# SparkFun_ESP8266_Thing_v10.net
KiCad netlist of a schematic drawn in EAGLE
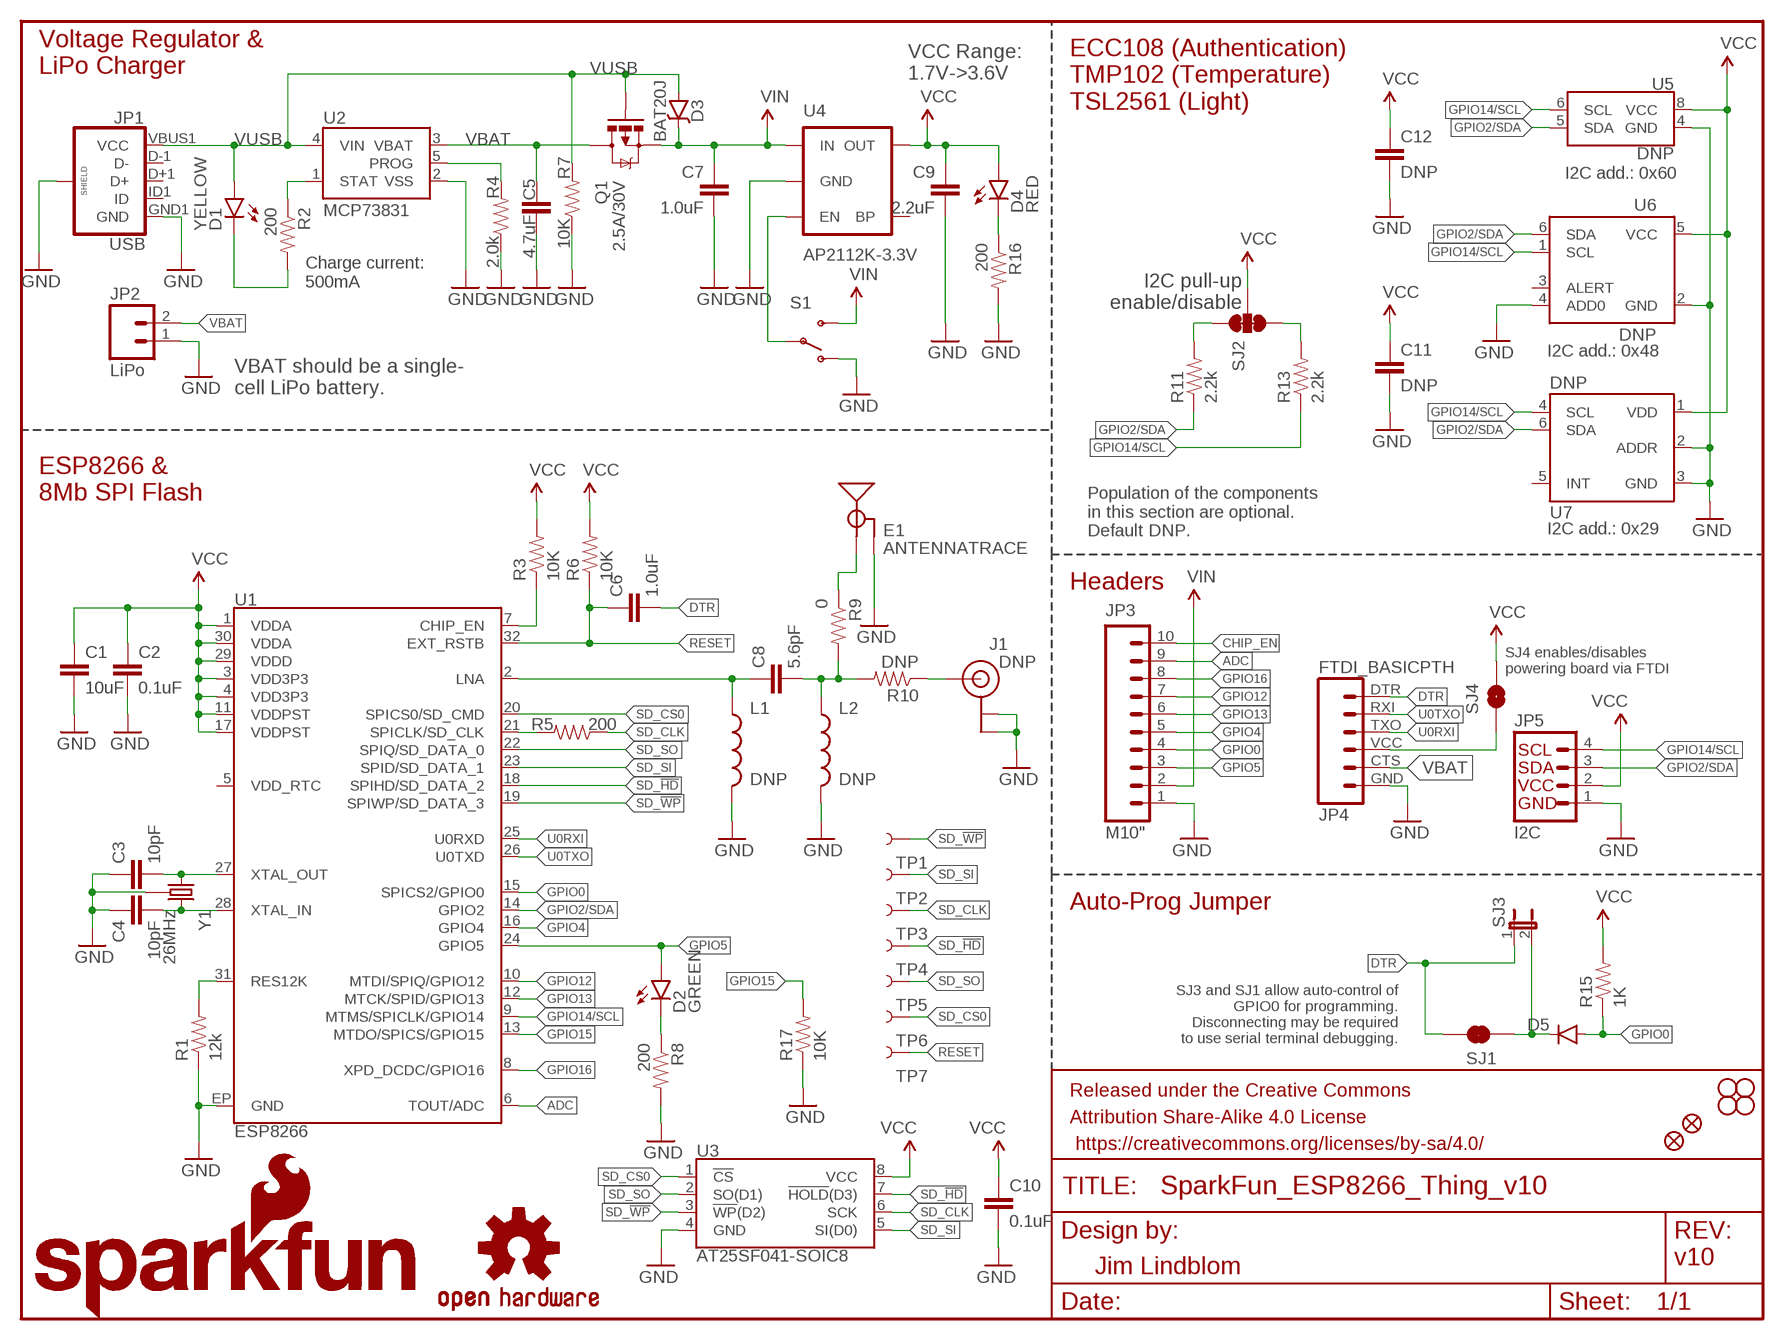
[diagram p0: schematic, sheet 1]

(export (version "E")
  (design (tool "Eeschema 10.0.6"))
  (components
    (comp (ref "C1")
      (value "10uF")
      (footprint "eagle-import:0603-CAP")
      (libsource (lib "eagle-import") (part "10UF-6.3V-20%(0603)"))
    )
    (comp (ref "C2")
      (value "0.1uF")
      (footprint "eagle-import:0603-CAP")
      (libsource (lib "eagle-import") (part "0.1UF-25V(+80/-20%)(0603)"))
    )
    (comp (ref "C3")
      (value "10pF")
      (footprint "eagle-import:0603-CAP")
      (libsource (lib "eagle-import") (part "10PF-50V-5%(0603)"))
    )
    (comp (ref "C4")
      (value "10pF")
      (footprint "eagle-import:0603-CAP")
      (libsource (lib "eagle-import") (part "10PF-50V-5%(0603)"))
    )
    (comp (ref "C5")
      (value "4.7uF")
      (footprint "eagle-import:0603-CAP")
      (libsource (lib "eagle-import") (part "4.7UF-6.3V-10%(0603)0603"))
    )
    (comp (ref "C6")
      (value "1.0uF")
      (footprint "eagle-import:0603-CAP")
      (libsource (lib "eagle-import") (part "1.0UF-16V-10%(0603)"))
    )
    (comp (ref "C7")
      (value "1.0uF")
      (footprint "eagle-import:0805")
      (libsource (lib "eagle-import") (part "1.0UF-25V-+80/-20(0805)"))
    )
    (comp (ref "C8")
      (value "5.6pF")
      (footprint "eagle-import:0603-CAP")
      (libsource (lib "eagle-import") (part "CAP0603-CAP"))
    )
    (comp (ref "C9")
      (value "2.2uF")
      (footprint "eagle-import:0603-CAP")
      (libsource (lib "eagle-import") (part "2.2UF-10V-20%(0603)"))
    )
    (comp (ref "C10")
      (value "0.1uF")
      (footprint "eagle-import:0603-CAP")
      (libsource (lib "eagle-import") (part "0.1UF-25V(+80/-20%)(0603)"))
    )
    (comp (ref "C11")
      (value "DNP")
      (footprint "eagle-import:0603-CAP")
      (libsource (lib "eagle-import") (part "0.1UF-25V(+80/-20%)(0603)"))
    )
    (comp (ref "C12")
      (value "DNP")
      (footprint "eagle-import:0603-CAP")
      (libsource (lib "eagle-import") (part "0.1UF-25V(+80/-20%)(0603)"))
    )
    (comp (ref "D1")
      (value "YELLOW")
      (footprint "eagle-import:LED-0603")
      (libsource (lib "eagle-import") (part "LED-YELLOW0603"))
    )
    (comp (ref "D2")
      (value "GREEN")
      (footprint "eagle-import:LED-0603")
      (libsource (lib "eagle-import") (part "LED-GREEN0603"))
    )
    (comp (ref "D3")
      (value "BAT20J")
      (footprint "eagle-import:SOD-323")
      (libsource (lib "eagle-import") (part "DIODE-SCHOTTKY-BAT20J"))
    )
    (comp (ref "D4")
      (value "RED")
      (footprint "eagle-import:LED-0603")
      (libsource (lib "eagle-import") (part "LED-RED0603"))
    )
    (comp (ref "D5")
      (value "DIODEBAS16")
      (footprint "eagle-import:SOD-323")
      (libsource (lib "eagle-import") (part "DIODEBAS16"))
    )
    (comp (ref "E1")
      (value "ANTENNATRACE")
      (footprint "eagle-import:TRACE_ANTENNA_2.4GHZ_25.7MM")
      (libsource (lib "eagle-import") (part "ANTENNATRACE"))
    )
    (comp (ref "FID1")
      (value "FIDUCIAL1X2")
      (footprint "eagle-import:FIDUCIAL-1X2")
      (libsource (lib "eagle-import") (part "FIDUCIAL1X2"))
    )
    (comp (ref "FID2")
      (value "FIDUCIAL1X2")
      (footprint "eagle-import:FIDUCIAL-1X2")
      (libsource (lib "eagle-import") (part "FIDUCIAL1X2"))
    )
    (comp (ref "FRAME1")
      (value "FRAME-LETTER")
      (footprint "eagle-import:CREATIVE_COMMONS")
      (libsource (lib "eagle-import") (part "FRAME-LETTER"))
    )
    (comp (ref "J1")
      (value "DNP")
      (footprint "eagle-import:U.FL")
      (libsource (lib "eagle-import") (part "U.FL"))
    )
    (comp (ref "JP1")
      (value "USB")
      (footprint "eagle-import:USB-B-MICRO-SMD_V03")
      (libsource (lib "eagle-import") (part "USB_MICROB_PLUGCONN-11752"))
    )
    (comp (ref "JP2")
      (value "LiPo")
      (footprint "eagle-import:JST-2-PTH")
      (libsource (lib "eagle-import") (part "M02JST-PTH-2"))
    )
    (comp (ref "JP3")
      (value "M10\"")
      (footprint "eagle-import:1X10")
      (libsource (lib "eagle-import") (part "M10{dblquote}"))
    )
    (comp (ref "JP4")
      (value "FTDI_BASICPTH")
      (footprint "eagle-import:FTDI_BASIC")
      (libsource (lib "eagle-import") (part "FTDI_BASICPTH"))
    )
    (comp (ref "JP5")
      (value "I2C")
      (footprint "eagle-import:1X04")
      (libsource (lib "eagle-import") (part "I2C_STANDARD"))
    )
    (comp (ref "L1")
      (value "DNP")
      (footprint "eagle-import:0603")
      (libsource (lib "eagle-import") (part "INDUCTOR0603"))
    )
    (comp (ref "L2")
      (value "DNP")
      (footprint "eagle-import:0603")
      (libsource (lib "eagle-import") (part "INDUCTOR0603"))
    )
    (comp (ref "LOGO1")
      (value "SFE_LOGO_NAME.2_INCH")
      (footprint "eagle-import:SFE_LOGO_NAME_.2")
      (libsource (lib "eagle-import") (part "SFE_LOGO_NAME.2_INCH"))
    )
    (comp (ref "LOGO3")
      (value "SFE_LOGO_FLAME.1_INCH")
      (footprint "eagle-import:SFE_LOGO_FLAME_.1")
      (libsource (lib "eagle-import") (part "SFE_LOGO_FLAME.1_INCH"))
    )
    (comp (ref "LOGO4")
      (value "OSHW-LOGOS")
      (footprint "eagle-import:OSHW-LOGO-S")
      (libsource (lib "eagle-import") (part "OSHW-LOGOS"))
    )
    (comp (ref "Q1")
      (value "2.5A/30V")
      (footprint "eagle-import:SOT23-3")
      (libsource (lib "eagle-import") (part "MOSFET-PCHANNELDMG2307L"))
    )
    (comp (ref "R1")
      (value "12k")
      (footprint "eagle-import:0603-RES")
      (libsource (lib "eagle-import") (part "12KOHM-1/10W-1%(0603)"))
    )
    (comp (ref "R2")
      (value "200")
      (footprint "eagle-import:0603-RES")
      (libsource (lib "eagle-import") (part "200OHM1/10W1%(0603)"))
    )
    (comp (ref "R3")
      (value "10K")
      (footprint "eagle-import:0603-RES")
      (libsource (lib "eagle-import") (part "10KOHM1/10W1%(0603)0603"))
    )
    (comp (ref "R4")
      (value "2.0k")
      (footprint "eagle-import:0603-RES")
      (libsource (lib "eagle-import") (part "2.0KOHM1/10W5%(0603)"))
    )
    (comp (ref "R5")
      (value "200")
      (footprint "eagle-import:0603-RES")
      (libsource (lib "eagle-import") (part "200OHM1/10W1%(0603)"))
    )
    (comp (ref "R6")
      (value "10K")
      (footprint "eagle-import:0603-RES")
      (libsource (lib "eagle-import") (part "10KOHM1/10W1%(0603)0603"))
    )
    (comp (ref "R7")
      (value "10K")
      (footprint "eagle-import:0603-RES")
      (libsource (lib "eagle-import") (part "10KOHM1/10W1%(0603)0603"))
    )
    (comp (ref "R8")
      (value "200")
      (footprint "eagle-import:0603-RES")
      (libsource (lib "eagle-import") (part "200OHM1/10W1%(0603)"))
    )
    (comp (ref "R9")
      (value "0")
      (footprint "eagle-import:0603")
      (libsource (lib "eagle-import") (part "0OHM1/10W5%(0603)"))
    )
    (comp (ref "R10")
      (value "DNP")
      (footprint "eagle-import:0603-RES")
      (libsource (lib "eagle-import") (part "RESISTOR0603-RES"))
    )
    (comp (ref "R11")
      (value "2.2k")
      (footprint "eagle-import:0603-RES")
      (libsource (lib "eagle-import") (part "2.2KOHM1/10W1%(0603)"))
    )
    (comp (ref "R13")
      (value "2.2k")
      (footprint "eagle-import:0603-RES")
      (libsource (lib "eagle-import") (part "2.2KOHM1/10W1%(0603)"))
    )
    (comp (ref "R15")
      (value "1K")
      (footprint "eagle-import:0603-RES")
      (libsource (lib "eagle-import") (part "1KOHM1/10W1%(0603)"))
    )
    (comp (ref "R16")
      (value "200")
      (footprint "eagle-import:0603-RES")
      (libsource (lib "eagle-import") (part "200OHM1/10W1%(0603)"))
    )
    (comp (ref "R17")
      (value "10K")
      (footprint "eagle-import:0603-RES")
      (libsource (lib "eagle-import") (part "10KOHM1/10W1%(0603)0603"))
    )
    (comp (ref "S1")
      (value "SWITCH-SPDT-SMD-A")
      (footprint "eagle-import:SWITCH-SPST-SMD-A")
      (libsource (lib "eagle-import") (part "SWITCH-SPDT-SMD-A"))
    )
    (comp (ref "SJ1")
      (value "JUMPER-PAD-2-NC_BY_TRACE")
      (footprint "eagle-import:PAD-JUMPER-2-NC_BY_TRACE_YES_SILK")
      (libsource (lib "eagle-import") (part "JUMPER-PAD-2-NC_BY_TRACE"))
    )
    (comp (ref "SJ2")
      (value "JUMPER-PAD-3-NC_BY_TRACE")
      (footprint "eagle-import:PAD-JUMPER-3-3OF3_NC_BY_TRACE_YES_SILK_FULL_BOX")
      (libsource (lib "eagle-import") (part "JUMPER-PAD-3-NC_BY_TRACE"))
    )
    (comp (ref "SJ3")
      (value "JUMPER-PTH-2-NC")
      (footprint "eagle-import:PTH-JUMPER-NC_BOTTOM_NO_SILK")
      (libsource (lib "eagle-import") (part "JUMPER-PTH-2-NC"))
    )
    (comp (ref "SJ4")
      (value "JUMPER-PAD-2-NOYES_SILK")
      (footprint "eagle-import:PAD-JUMPER-2-NO_YES_SILK")
      (libsource (lib "eagle-import") (part "JUMPER-PAD-2-NOYES_SILK"))
    )
    (comp (ref "STANDOFF1")
      (value "STAND-OFF")
      (footprint "eagle-import:STAND-OFF")
      (libsource (lib "eagle-import") (part "STAND-OFF"))
    )
    (comp (ref "STANDOFF2")
      (value "STAND-OFF")
      (footprint "eagle-import:STAND-OFF")
      (libsource (lib "eagle-import") (part "STAND-OFF"))
    )
    (comp (ref "STANDOFF3")
      (value "STAND-OFF")
      (footprint "eagle-import:STAND-OFF")
      (libsource (lib "eagle-import") (part "STAND-OFF"))
    )
    (comp (ref "STANDOFF4")
      (value "STAND-OFF")
      (footprint "eagle-import:STAND-OFF")
      (libsource (lib "eagle-import") (part "STAND-OFF"))
    )
    (comp (ref "TP1")
      (value "TEST-POINT3X5")
      (footprint "eagle-import:PAD.03X.05")
      (libsource (lib "eagle-import") (part "TEST-POINT3X5"))
    )
    (comp (ref "TP2")
      (value "TEST-POINT3X5")
      (footprint "eagle-import:PAD.03X.05")
      (libsource (lib "eagle-import") (part "TEST-POINT3X5"))
    )
    (comp (ref "TP3")
      (value "TEST-POINT3X5")
      (footprint "eagle-import:PAD.03X.05")
      (libsource (lib "eagle-import") (part "TEST-POINT3X5"))
    )
    (comp (ref "TP4")
      (value "TEST-POINT3X5")
      (footprint "eagle-import:PAD.03X.05")
      (libsource (lib "eagle-import") (part "TEST-POINT3X5"))
    )
    (comp (ref "TP5")
      (value "TEST-POINT3X5")
      (footprint "eagle-import:PAD.03X.05")
      (libsource (lib "eagle-import") (part "TEST-POINT3X5"))
    )
    (comp (ref "TP6")
      (value "TEST-POINT3X5")
      (footprint "eagle-import:PAD.03X.05")
      (libsource (lib "eagle-import") (part "TEST-POINT3X5"))
    )
    (comp (ref "TP7")
      (value "TEST-POINT3X5")
      (footprint "eagle-import:PAD.03X.05")
      (libsource (lib "eagle-import") (part "TEST-POINT3X5"))
    )
    (comp (ref "U1")
      (value "ESP8266")
      (footprint "eagle-import:QFN32")
      (libsource (lib "eagle-import") (part "ESP8266"))
    )
    (comp (ref "U2")
      (value "MCP73831")
      (footprint "eagle-import:SOT23-5")
      (libsource (lib "eagle-import") (part "MCP73831"))
    )
    (comp (ref "U3")
      (value "AT25SF041-SOIC8")
      (footprint "eagle-import:SO08")
      (libsource (lib "eagle-import") (part "AT25SF041-SOIC8"))
    )
    (comp (ref "U4")
      (value "AP2112K-3.3V")
      (footprint "eagle-import:SOT23-5")
      (libsource (lib "eagle-import") (part "V_REG_LDOSMD"))
    )
    (comp (ref "U5")
      (value "DNP")
      (footprint "eagle-import:UDFN8")
      (libsource (lib "eagle-import") (part "ATECC108-MAHDA"))
    )
    (comp (ref "U6")
      (value "DNP")
      (footprint "eagle-import:SOT563-2")
      (libsource (lib "eagle-import") (part "TMP1021{colon}1"))
    )
    (comp (ref "U7")
      (value "DNP")
      (footprint "eagle-import:FN-6")
      (libsource (lib "eagle-import") (part "TSL2561FN"))
    )
    (comp (ref "Y1")
      (value "26MHz")
      (footprint "eagle-import:CRYSTAL-SMD-3.2X2.5")
      (libsource (lib "eagle-import") (part "CRYSTAL-GROUNDED3.2X2.5"))
    )
  )
  (nets
    (net (code "1") (name "/SD_~{HD}") (class "Default")
      (node (ref "TP4") (pin "P$1") (pinfunction "1_P$1") (pintype "bidirectional"))
      (node (ref "U1") (pin "18") (pinfunction "SPIHD/SD_DATA_2_18") (pintype "bidirectional"))
      (node (ref "U3") (pin "7") (pinfunction "~{HOLD}(D3)_7") (pintype "bidirectional"))
    )
    (net (code "2") (name "/SD_~{WP}") (class "Default")
      (node (ref "TP1") (pin "P$1") (pinfunction "1_P$1") (pintype "bidirectional"))
      (node (ref "U1") (pin "19") (pinfunction "SPIWP/SD_DATA_3_19") (pintype "bidirectional"))
      (node (ref "U3") (pin "3") (pinfunction "~{WP}(D2)_3") (pintype "bidirectional"))
    )
    (net (code "3") (name "/VUSB") (class "Default")
      (node (ref "D1") (pin "A") (pinfunction "A_A") (pintype "passive"))
      (node (ref "D3") (pin "A") (pinfunction "A_A") (pintype "passive"))
      (node (ref "JP1") (pin "VBUS1") (pinfunction "VCC_VBUS1") (pintype "bidirectional"))
      (node (ref "Q1") (pin "1") (pinfunction "G_1") (pintype "passive"))
      (node (ref "R7") (pin "2") (pinfunction "2_2") (pintype "passive"))
      (node (ref "U2") (pin "4") (pinfunction "VIN_4") (pintype "power_in"))
    )
    (net (code "4") (name "ADC") (class "Default")
      (node (ref "JP3") (pin "9") (pinfunction "9_9") (pintype "passive"))
      (node (ref "U1") (pin "6") (pinfunction "TOUT/ADC_6") (pintype "bidirectional"))
    )
    (net (code "5") (name "CHIP_EN") (class "Default")
      (node (ref "JP3") (pin "10") (pinfunction "10_10") (pintype "passive"))
      (node (ref "R3") (pin "1") (pinfunction "1_1") (pintype "passive"))
      (node (ref "U1") (pin "7") (pinfunction "CHIP_EN_7") (pintype "bidirectional"))
    )
    (net (code "6") (name "DTR") (class "Default")
      (node (ref "C6") (pin "2") (pinfunction "2_2") (pintype "passive"))
      (node (ref "JP4") (pin "DTR") (pinfunction "1_DTR") (pintype "passive"))
      (node (ref "SJ1") (pin "2") (pinfunction "2_2") (pintype "passive"))
      (node (ref "SJ3") (pin "1") (pinfunction "1_1") (pintype "passive"))
    )
    (net (code "7") (name "GND") (class "Default")
      (node (ref "C1") (pin "2") (pinfunction "2_2") (pintype "passive"))
      (node (ref "C10") (pin "2") (pinfunction "2_2") (pintype "passive"))
      (node (ref "C11") (pin "2") (pinfunction "2_2") (pintype "passive"))
      (node (ref "C12") (pin "2") (pinfunction "2_2") (pintype "passive"))
      (node (ref "C2") (pin "2") (pinfunction "2_2") (pintype "passive"))
      (node (ref "C3") (pin "1") (pinfunction "1_1") (pintype "passive"))
      (node (ref "C4") (pin "1") (pinfunction "1_1") (pintype "passive"))
      (node (ref "C5") (pin "2") (pinfunction "2_2") (pintype "passive"))
      (node (ref "C7") (pin "2") (pinfunction "2_2") (pintype "passive"))
      (node (ref "C9") (pin "2") (pinfunction "2_2") (pintype "passive"))
      (node (ref "E1") (pin "GND") (pinfunction "GND_GND") (pintype "bidirectional"))
      (node (ref "E1") (pin "GND2") (pinfunction "GND_GND2") (pintype "bidirectional"))
      (node (ref "J1") (pin "P$1") (pinfunction "GND_P$1") (pintype "bidirectional"))
      (node (ref "J1") (pin "P$2") (pinfunction "GND_P$2") (pintype "bidirectional"))
      (node (ref "JP1") (pin "GND1") (pinfunction "GND_GND1") (pintype "bidirectional"))
      (node (ref "JP1") (pin "SHIELD1") (pinfunction "SHIELD_SHIELD1") (pintype "bidirectional"))
      (node (ref "JP1") (pin "SHIELD2") (pinfunction "SHIELD_SHIELD2") (pintype "bidirectional"))
      (node (ref "JP1") (pin "SHIELD3") (pinfunction "SHIELD_SHIELD3") (pintype "bidirectional"))
      (node (ref "JP2") (pin "1") (pinfunction "1_1") (pintype "passive"))
      (node (ref "JP3") (pin "1") (pinfunction "1_1") (pintype "passive"))
      (node (ref "JP4") (pin "GND") (pinfunction "6_GND") (pintype "passive"))
      (node (ref "JP5") (pin "1") (pinfunction "1_1") (pintype "passive"))
      (node (ref "L1") (pin "2") (pinfunction "2_2") (pintype "passive"))
      (node (ref "L2") (pin "2") (pinfunction "2_2") (pintype "passive"))
      (node (ref "R1") (pin "1") (pinfunction "1_1") (pintype "passive"))
      (node (ref "R16") (pin "2") (pinfunction "2_2") (pintype "passive"))
      (node (ref "R17") (pin "1") (pinfunction "1_1") (pintype "passive"))
      (node (ref "R4") (pin "1") (pinfunction "1_1") (pintype "passive"))
      (node (ref "R7") (pin "1") (pinfunction "1_1") (pintype "passive"))
      (node (ref "R8") (pin "2") (pinfunction "2_2") (pintype "passive"))
      (node (ref "S1") (pin "1") (pinfunction "O_1") (pintype "passive"))
      (node (ref "U1") (pin "EP") (pinfunction "GND_EP") (pintype "bidirectional"))
      (node (ref "U2") (pin "2") (pinfunction "VSS_2") (pintype "power_in"))
      (node (ref "U3") (pin "4") (pinfunction "GND_4") (pintype "bidirectional"))
      (node (ref "U4") (pin "2") (pinfunction "GND_2") (pintype "input"))
      (node (ref "U5") (pin "4") (pinfunction "GND_4") (pintype "bidirectional"))
      (node (ref "U6") (pin "2") (pinfunction "GND_2") (pintype "bidirectional"))
      (node (ref "U6") (pin "4") (pinfunction "ADD0_4") (pintype "bidirectional"))
      (node (ref "U7") (pin "2") (pinfunction "ADDR_2") (pintype "input"))
      (node (ref "U7") (pin "3") (pinfunction "GND_3") (pintype "power_in"))
      (node (ref "Y1") (pin "2") (pinfunction "GND_2") (pintype "passive"))
      (node (ref "Y1") (pin "4") (pinfunction "GND_4") (pintype "passive"))
    )
    (net (code "8") (name "GPIO0") (class "Default")
      (node (ref "D5") (pin "A") (pinfunction "A_A") (pintype "passive"))
      (node (ref "JP3") (pin "4") (pinfunction "4_4") (pintype "passive"))
      (node (ref "R15") (pin "1") (pinfunction "1_1") (pintype "passive"))
      (node (ref "U1") (pin "15") (pinfunction "SPICS2/GPIO0_15") (pintype "bidirectional"))
    )
    (net (code "9") (name "GPIO2{slash}SDA") (class "Default")
      (node (ref "JP5") (pin "3") (pinfunction "3_3") (pintype "passive"))
      (node (ref "R11") (pin "1") (pinfunction "1_1") (pintype "passive"))
      (node (ref "U1") (pin "14") (pinfunction "GPIO2_14") (pintype "bidirectional"))
      (node (ref "U5") (pin "5") (pinfunction "SDA_5") (pintype "bidirectional"))
      (node (ref "U6") (pin "6") (pinfunction "SDA_6") (pintype "bidirectional"))
      (node (ref "U7") (pin "6") (pinfunction "SDA_6") (pintype "bidirectional"))
    )
    (net (code "10") (name "GPIO4") (class "Default")
      (node (ref "JP3") (pin "5") (pinfunction "5_5") (pintype "passive"))
      (node (ref "U1") (pin "16") (pinfunction "GPIO4_16") (pintype "bidirectional"))
    )
    (net (code "11") (name "GPIO5") (class "Default")
      (node (ref "D2") (pin "A") (pinfunction "A_A") (pintype "passive"))
      (node (ref "JP3") (pin "3") (pinfunction "3_3") (pintype "passive"))
      (node (ref "U1") (pin "24") (pinfunction "GPIO5_24") (pintype "bidirectional"))
    )
    (net (code "12") (name "GPIO12") (class "Default")
      (node (ref "JP3") (pin "7") (pinfunction "7_7") (pintype "passive"))
      (node (ref "U1") (pin "10") (pinfunction "MTDI/SPIQ/GPIO12_10") (pintype "bidirectional"))
    )
    (net (code "13") (name "GPIO13") (class "Default")
      (node (ref "JP3") (pin "6") (pinfunction "6_6") (pintype "passive"))
      (node (ref "U1") (pin "12") (pinfunction "MTCK/SPID/GPIO13_12") (pintype "bidirectional"))
    )
    (net (code "14") (name "GPIO14{slash}SCL") (class "Default")
      (node (ref "JP5") (pin "4") (pinfunction "4_4") (pintype "passive"))
      (node (ref "R13") (pin "1") (pinfunction "1_1") (pintype "passive"))
      (node (ref "U1") (pin "9") (pinfunction "MTMS/SPICLK/GPIO14_9") (pintype "bidirectional"))
      (node (ref "U5") (pin "6") (pinfunction "SCL_6") (pintype "bidirectional"))
      (node (ref "U6") (pin "1") (pinfunction "SCL_1") (pintype "bidirectional"))
      (node (ref "U7") (pin "4") (pinfunction "SCL_4") (pintype "input"))
    )
    (net (code "15") (name "GPIO15") (class "Default")
      (node (ref "R17") (pin "2") (pinfunction "2_2") (pintype "passive"))
      (node (ref "U1") (pin "13") (pinfunction "MTDO/SPICS/GPIO15_13") (pintype "bidirectional"))
    )
    (net (code "16") (name "GPIO16") (class "Default")
      (node (ref "JP3") (pin "8") (pinfunction "8_8") (pintype "passive"))
      (node (ref "U1") (pin "8") (pinfunction "XPD_DCDC/GPIO16_8") (pintype "bidirectional"))
    )
    (net (code "17") (name "Net-(C8-Pad2)") (class "Default")
      (node (ref "C8") (pin "2") (pinfunction "2_2") (pintype "passive"))
      (node (ref "L2") (pin "1") (pinfunction "1_1") (pintype "passive"))
      (node (ref "R10") (pin "2") (pinfunction "2_2") (pintype "passive"))
      (node (ref "R9") (pin "2") (pinfunction "2_2") (pintype "passive"))
    )
    (net (code "18") (name "Net-(D1-PadC)") (class "Default")
      (node (ref "D1") (pin "C") (pinfunction "C_C") (pintype "passive"))
      (node (ref "R2") (pin "2") (pinfunction "2_2") (pintype "passive"))
    )
    (net (code "19") (name "Net-(D2-PadC)") (class "Default")
      (node (ref "D2") (pin "C") (pinfunction "C_C") (pintype "passive"))
      (node (ref "R8") (pin "1") (pinfunction "1_1") (pintype "passive"))
    )
    (net (code "20") (name "Net-(D4-PadC)") (class "Default")
      (node (ref "D4") (pin "C") (pinfunction "C_C") (pintype "passive"))
      (node (ref "R16") (pin "1") (pinfunction "1_1") (pintype "passive"))
    )
    (net (code "21") (name "Net-(D5-PadC)") (class "Default")
      (node (ref "D5") (pin "C") (pinfunction "C_C") (pintype "passive"))
      (node (ref "SJ1") (pin "1") (pinfunction "1_1") (pintype "passive"))
      (node (ref "SJ3") (pin "2") (pinfunction "2_2") (pintype "passive"))
    )
    (net (code "22") (name "Net-(E1-SIGNAL)") (class "Default")
      (node (ref "E1") (pin "ANT") (pinfunction "SIGNAL_ANT") (pintype "bidirectional"))
      (node (ref "R9") (pin "1") (pinfunction "1_1") (pintype "passive"))
    )
    (net (code "23") (name "Net-(J1-SIGNAL)") (class "Default")
      (node (ref "J1") (pin "P$3") (pinfunction "SIGNAL_P$3") (pintype "bidirectional"))
      (node (ref "R10") (pin "1") (pinfunction "1_1") (pintype "passive"))
    )
    (net (code "24") (name "Net-(JP4-4)") (class "Default")
      (node (ref "JP4") (pin "VCC") (pinfunction "4_VCC") (pintype "passive"))
      (node (ref "SJ4") (pin "1") (pinfunction "1_1") (pintype "passive"))
    )
    (net (code "25") (name "Net-(R11-Pad2)") (class "Default")
      (node (ref "R11") (pin "2") (pinfunction "2_2") (pintype "passive"))
      (node (ref "SJ2") (pin "1") (pinfunction "1_1") (pintype "passive"))
    )
    (net (code "26") (name "Net-(R13-Pad2)") (class "Default")
      (node (ref "R13") (pin "2") (pinfunction "2_2") (pintype "passive"))
      (node (ref "SJ2") (pin "3") (pinfunction "3_3") (pintype "passive"))
    )
    (net (code "27") (name "Net-(S1-P)") (class "Default")
      (node (ref "S1") (pin "2") (pinfunction "P_2") (pintype "passive"))
      (node (ref "U4") (pin "3") (pinfunction "EN_3") (pintype "input"))
    )
    (net (code "28") (name "Net-(U1-LNA)") (class "Default")
      (node (ref "C8") (pin "1") (pinfunction "1_1") (pintype "passive"))
      (node (ref "L1") (pin "1") (pinfunction "1_1") (pintype "passive"))
      (node (ref "U1") (pin "2") (pinfunction "LNA_2") (pintype "bidirectional"))
    )
    (net (code "29") (name "Net-(U1-RES12K)") (class "Default")
      (node (ref "R1") (pin "2") (pinfunction "2_2") (pintype "passive"))
      (node (ref "U1") (pin "31") (pinfunction "RES12K_31") (pintype "bidirectional"))
    )
    (net (code "30") (name "Net-(U1-SPICLK{slash}SD_CLK)") (class "Default")
      (node (ref "R5") (pin "2") (pinfunction "2_2") (pintype "passive"))
      (node (ref "U1") (pin "21") (pinfunction "SPICLK/SD_CLK_21") (pintype "bidirectional"))
    )
    (net (code "31") (name "Net-(U1-XTAL_IN)") (class "Default")
      (node (ref "C4") (pin "2") (pinfunction "2_2") (pintype "passive"))
      (node (ref "U1") (pin "28") (pinfunction "XTAL_IN_28") (pintype "bidirectional"))
      (node (ref "Y1") (pin "3") (pinfunction "2_3") (pintype "passive"))
    )
    (net (code "32") (name "Net-(U1-XTAL_OUT)") (class "Default")
      (node (ref "C3") (pin "2") (pinfunction "2_2") (pintype "passive"))
      (node (ref "U1") (pin "27") (pinfunction "XTAL_OUT_27") (pintype "bidirectional"))
      (node (ref "Y1") (pin "1") (pinfunction "1_1") (pintype "passive"))
    )
    (net (code "33") (name "Net-(U2-PROG)") (class "Default")
      (node (ref "R4") (pin "2") (pinfunction "2_2") (pintype "passive"))
      (node (ref "U2") (pin "5") (pinfunction "PROG_5") (pintype "input"))
    )
    (net (code "34") (name "Net-(U2-STAT)") (class "Default")
      (node (ref "R2") (pin "1") (pinfunction "1_1") (pintype "passive"))
      (node (ref "U2") (pin "1") (pinfunction "STAT_1") (pintype "output"))
    )
    (net (code "35") (name "RESET") (class "Default")
      (node (ref "C6") (pin "1") (pinfunction "1_1") (pintype "passive"))
      (node (ref "R6") (pin "1") (pinfunction "1_1") (pintype "passive"))
      (node (ref "TP7") (pin "P$1") (pinfunction "1_P$1") (pintype "bidirectional"))
      (node (ref "U1") (pin "32") (pinfunction "EXT_RSTB_32") (pintype "bidirectional"))
    )
    (net (code "36") (name "SD_CLK") (class "Default")
      (node (ref "R5") (pin "1") (pinfunction "1_1") (pintype "passive"))
      (node (ref "TP3") (pin "P$1") (pinfunction "1_P$1") (pintype "bidirectional"))
      (node (ref "U3") (pin "6") (pinfunction "SCK_6") (pintype "bidirectional"))
    )
    (net (code "37") (name "SD_CS0") (class "Default")
      (node (ref "TP6") (pin "P$1") (pinfunction "1_P$1") (pintype "bidirectional"))
      (node (ref "U1") (pin "20") (pinfunction "SPICS0/SD_CMD_20") (pintype "bidirectional"))
      (node (ref "U3") (pin "1") (pinfunction "~{CS}_1") (pintype "bidirectional"))
    )
    (net (code "38") (name "SD_SI") (class "Default")
      (node (ref "TP2") (pin "P$1") (pinfunction "1_P$1") (pintype "bidirectional"))
      (node (ref "U1") (pin "23") (pinfunction "SPID/SD_DATA_1_23") (pintype "bidirectional"))
      (node (ref "U3") (pin "5") (pinfunction "SI(D0)_5") (pintype "bidirectional"))
    )
    (net (code "39") (name "SD_SO") (class "Default")
      (node (ref "TP5") (pin "P$1") (pinfunction "1_P$1") (pintype "bidirectional"))
      (node (ref "U1") (pin "22") (pinfunction "SPIQ/SD_DATA_0_22") (pintype "bidirectional"))
      (node (ref "U3") (pin "2") (pinfunction "SO(D1)_2") (pintype "bidirectional"))
    )
    (net (code "40") (name "U0RXI") (class "Default")
      (node (ref "JP4") (pin "TXO") (pinfunction "3_TXO") (pintype "passive"))
      (node (ref "U1") (pin "25") (pinfunction "U0RXD_25") (pintype "bidirectional"))
    )
    (net (code "41") (name "U0TXO") (class "Default")
      (node (ref "JP4") (pin "RXI") (pinfunction "2_RXI") (pintype "passive"))
      (node (ref "U1") (pin "26") (pinfunction "U0TXD_26") (pintype "bidirectional"))
    )
    (net (code "42") (name "VBAT") (class "Default")
      (node (ref "C5") (pin "1") (pinfunction "1_1") (pintype "passive"))
      (node (ref "JP2") (pin "2") (pinfunction "2_2") (pintype "passive"))
      (node (ref "JP4") (pin "CTS") (pinfunction "5_CTS") (pintype "passive"))
      (node (ref "Q1") (pin "3") (pinfunction "D_3") (pintype "passive"))
      (node (ref "U2") (pin "3") (pinfunction "VBAT_3") (pintype "power_in"))
    )
    (net (code "43") (name "VCC") (class "Default")
      (node (ref "C1") (pin "1") (pinfunction "1_1") (pintype "passive"))
      (node (ref "C10") (pin "1") (pinfunction "1_1") (pintype "passive"))
      (node (ref "C11") (pin "1") (pinfunction "1_1") (pintype "passive"))
      (node (ref "C12") (pin "1") (pinfunction "1_1") (pintype "passive"))
      (node (ref "C2") (pin "1") (pinfunction "1_1") (pintype "passive"))
      (node (ref "C9") (pin "1") (pinfunction "1_1") (pintype "passive"))
      (node (ref "D4") (pin "A") (pinfunction "A_A") (pintype "passive"))
      (node (ref "JP5") (pin "2") (pinfunction "2_2") (pintype "passive"))
      (node (ref "R15") (pin "2") (pinfunction "2_2") (pintype "passive"))
      (node (ref "R3") (pin "2") (pinfunction "2_2") (pintype "passive"))
      (node (ref "R6") (pin "2") (pinfunction "2_2") (pintype "passive"))
      (node (ref "SJ2") (pin "2") (pinfunction "2_2") (pintype "passive"))
      (node (ref "SJ4") (pin "2") (pinfunction "2_2") (pintype "passive"))
      (node (ref "U1") (pin "1") (pinfunction "VDDA_1") (pintype "bidirectional"))
      (node (ref "U1") (pin "11") (pinfunction "VDDPST_11") (pintype "bidirectional"))
      (node (ref "U1") (pin "17") (pinfunction "VDDPST_17") (pintype "bidirectional"))
      (node (ref "U1") (pin "29") (pinfunction "VDDD_29") (pintype "bidirectional"))
      (node (ref "U1") (pin "3") (pinfunction "VDD3P3_3") (pintype "bidirectional"))
      (node (ref "U1") (pin "30") (pinfunction "VDDA_30") (pintype "bidirectional"))
      (node (ref "U1") (pin "4") (pinfunction "VDD3P3_4") (pintype "bidirectional"))
      (node (ref "U3") (pin "8") (pinfunction "VCC_8") (pintype "bidirectional"))
      (node (ref "U4") (pin "5") (pinfunction "OUT_5") (pintype "passive"))
      (node (ref "U5") (pin "8") (pinfunction "VCC_8") (pintype "bidirectional"))
      (node (ref "U6") (pin "5") (pinfunction "VCC_5") (pintype "bidirectional"))
      (node (ref "U7") (pin "1") (pinfunction "VDD_1") (pintype "power_in"))
    )
    (net (code "44") (name "VIN") (class "Default")
      (node (ref "C7") (pin "1") (pinfunction "1_1") (pintype "passive"))
      (node (ref "D3") (pin "C") (pinfunction "C_C") (pintype "passive"))
      (node (ref "JP3") (pin "2") (pinfunction "2_2") (pintype "passive"))
      (node (ref "Q1") (pin "2") (pinfunction "S_2") (pintype "passive"))
      (node (ref "S1") (pin "3") (pinfunction "S_3") (pintype "passive"))
      (node (ref "U4") (pin "1") (pinfunction "IN_1") (pintype "input"))
    )
    (net (code "45") (name "unconnected-(JP1-D+-PadD+1)") (class "Default")
      (node (ref "JP1") (pin "D+1") (pinfunction "D+_D+1") (pintype "bidirectional"))
    )
    (net (code "46") (name "unconnected-(JP1-D--PadD-1)") (class "Default")
      (node (ref "JP1") (pin "D-1") (pinfunction "D-_D-1") (pintype "bidirectional"))
    )
    (net (code "47") (name "unconnected-(JP1-ID-PadID1)") (class "Default")
      (node (ref "JP1") (pin "ID1") (pinfunction "ID_ID1") (pintype "bidirectional"))
    )
    (net (code "48") (name "unconnected-(U1-VDD_RTC-Pad5)") (class "Default")
      (node (ref "U1") (pin "5") (pinfunction "VDD_RTC_5") (pintype "bidirectional"))
    )
    (net (code "49") (name "unconnected-(U4-BP-Pad4)") (class "Default")
      (node (ref "U4") (pin "4") (pinfunction "BP_4") (pintype "input"))
    )
    (net (code "50") (name "unconnected-(U6-ALERT-Pad3)") (class "Default")
      (node (ref "U6") (pin "3") (pinfunction "ALERT_3") (pintype "bidirectional"))
    )
    (net (code "51") (name "unconnected-(U7-INT-Pad5)") (class "Default")
      (node (ref "U7") (pin "5") (pinfunction "INT_5") (pintype "output"))
    )
  )
)
